# h-bridge_v2.net
KiCad netlist of a schematic drawn in EAGLE
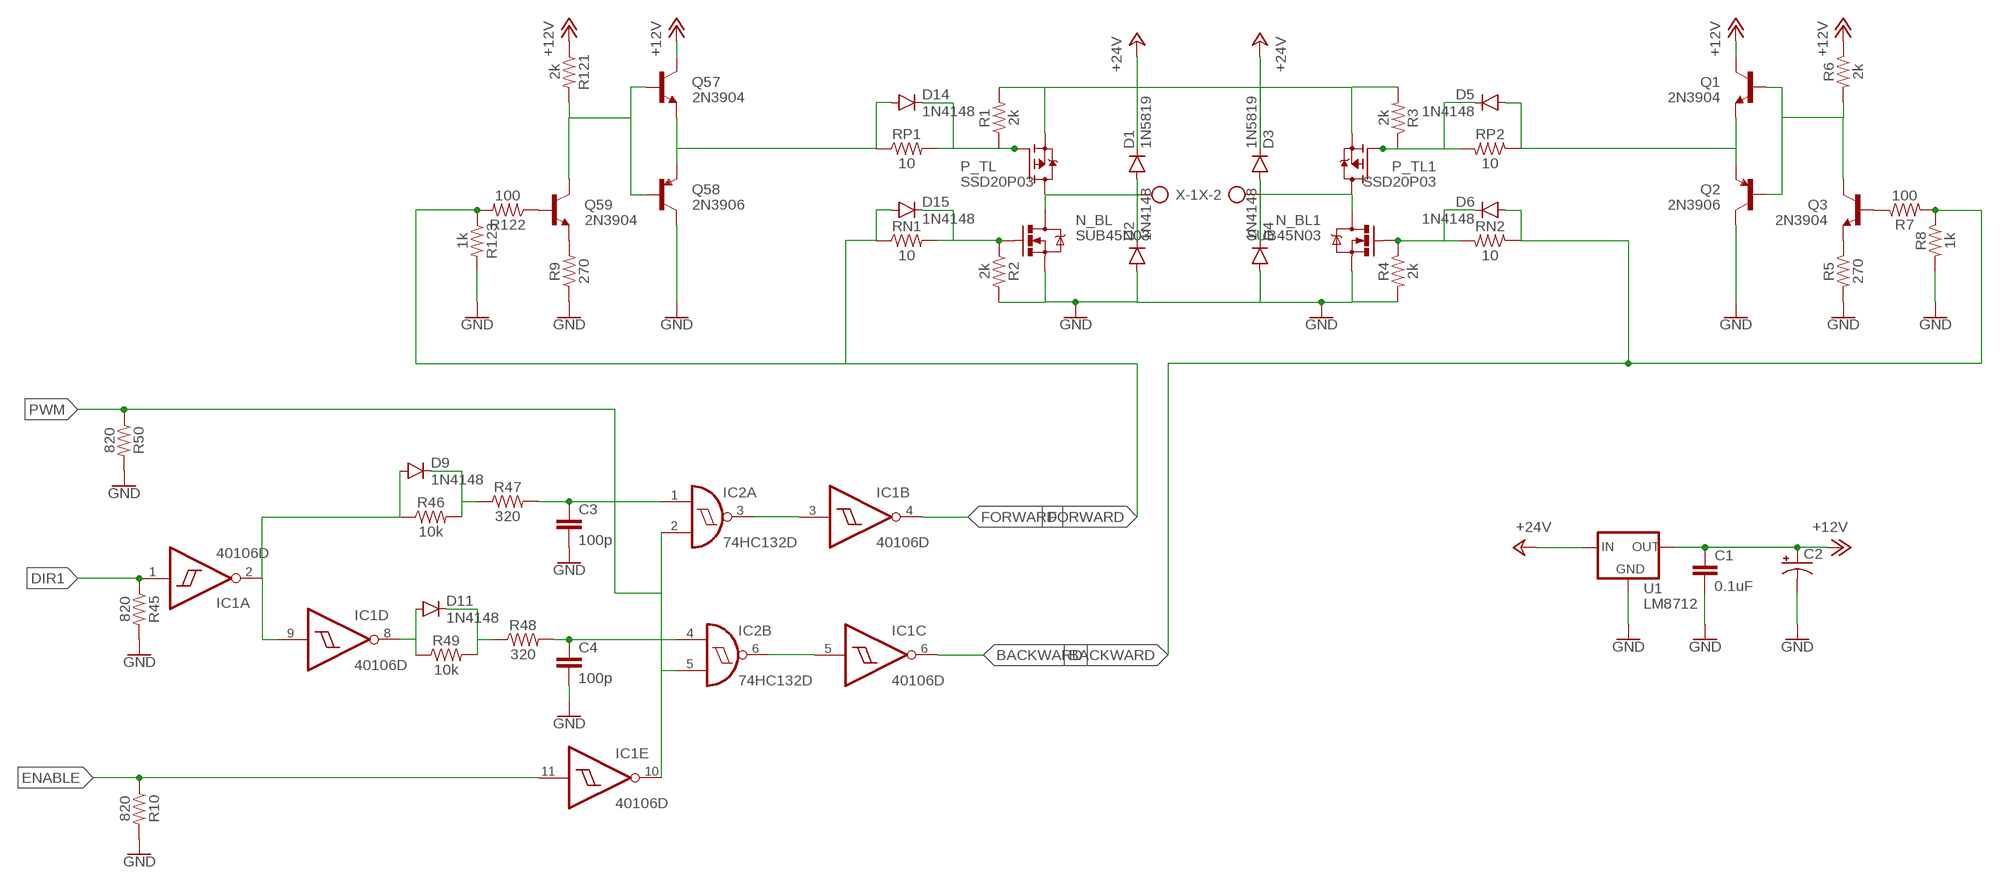
[diagram p0: schematic, sheet 1]

(export (version "E")
  (design (tool "Eeschema 10.0.6"))
  (components
    (comp (ref "C1")
      (value "0.1uF")
      (footprint "eagle-import:0603-CAP")
      (libsource (lib "eagle-import") (part "0.1UF-25V-5%(0603)"))
    )
    (comp (ref "C2")
      (value "CAP_POL1206-KIT")
      (footprint "eagle-import:EIA3216-KIT")
      (libsource (lib "eagle-import") (part "CAP_POL1206-KIT"))
    )
    (comp (ref "C3")
      (value "100p")
      (footprint "eagle-import:0805-CAP")
      (libsource (lib "eagle-import") (part "1.0UF-25V-+80/-20(0805){dblquote}"))
    )
    (comp (ref "C4")
      (value "100p")
      (footprint "eagle-import:0805-CAP")
      (libsource (lib "eagle-import") (part "1.0UF-25V-+80/-20(0805){dblquote}"))
    )
    (comp (ref "D1")
      (value "1N5819")
      (footprint "eagle-import:SOD-123")
      (libsource (lib "eagle-import") (part "DIODESOD123"))
    )
    (comp (ref "D2")
      (value "1N4148")
      (footprint "eagle-import:SOD-123")
      (libsource (lib "eagle-import") (part "DIODESOD123"))
    )
    (comp (ref "D3")
      (value "1N5819")
      (footprint "eagle-import:SOD-123")
      (libsource (lib "eagle-import") (part "DIODESOD123"))
    )
    (comp (ref "D4")
      (value "1N4148")
      (footprint "eagle-import:SOD-123")
      (libsource (lib "eagle-import") (part "DIODESOD123"))
    )
    (comp (ref "D5")
      (value "1N4148")
      (footprint "eagle-import:SOD-123")
      (libsource (lib "eagle-import") (part "DIODESOD123"))
    )
    (comp (ref "D6")
      (value "1N4148")
      (footprint "eagle-import:SOD-123")
      (libsource (lib "eagle-import") (part "DIODESOD123"))
    )
    (comp (ref "D9")
      (value "1N4148")
      (footprint "eagle-import:SOD-123")
      (libsource (lib "eagle-import") (part "DIODESOD123"))
    )
    (comp (ref "D11")
      (value "1N4148")
      (footprint "eagle-import:SOD-123")
      (libsource (lib "eagle-import") (part "DIODESOD123"))
    )
    (comp (ref "D14")
      (value "1N4148")
      (footprint "eagle-import:SOD-123")
      (libsource (lib "eagle-import") (part "DIODESOD123"))
    )
    (comp (ref "D15")
      (value "1N4148")
      (footprint "eagle-import:SOD-123")
      (libsource (lib "eagle-import") (part "DIODESOD123"))
    )
    (comp (ref "IC1")
      (value "40106D")
      (footprint "eagle-import:SO14")
      (libsource (lib "eagle-import") (part "40106D"))
    )
    (comp (ref "IC2")
      (value "74HC132D")
      (footprint "eagle-import:SO14")
      (libsource (lib "eagle-import") (part "74132DHC"))
    )
    (comp (ref "N_BL")
      (value "SUB45N03")
      (footprint "eagle-import:TO-263_D2PAK")
      (libsource (lib "eagle-import") (part "MOSFET-NCHANNELPSMN7R0"))
    )
    (comp (ref "N_BL1")
      (value "SUB45N03")
      (footprint "eagle-import:TO-263_D2PAK")
      (libsource (lib "eagle-import") (part "MOSFET-NCHANNELPSMN7R0"))
    )
    (comp (ref "P_TL")
      (value "SSD20P03")
      (footprint "eagle-import:TO252")
      (libsource (lib "eagle-import") (part "FDD4141TO252"))
    )
    (comp (ref "P_TL1")
      (value "SSD20P03")
      (footprint "eagle-import:TO252")
      (libsource (lib "eagle-import") (part "FDD4141TO252"))
    )
    (comp (ref "Q1")
      (value "2N3904")
      (footprint "eagle-import:SOT23-3")
      (libsource (lib "eagle-import") (part "TRANSISTOR_NPNMMBT5088"))
    )
    (comp (ref "Q2")
      (value "2N3906")
      (footprint "eagle-import:SOT23-3")
      (libsource (lib "eagle-import") (part "TRANSISTOR_PNPPMBT3906"))
    )
    (comp (ref "Q3")
      (value "2N3904")
      (footprint "eagle-import:SOT23-3")
      (libsource (lib "eagle-import") (part "TRANSISTOR_NPNMMBT5088"))
    )
    (comp (ref "Q57")
      (value "2N3904")
      (footprint "eagle-import:SOT23-3")
      (libsource (lib "eagle-import") (part "TRANSISTOR_NPNMMBT5088"))
    )
    (comp (ref "Q58")
      (value "2N3906")
      (footprint "eagle-import:SOT23-3")
      (libsource (lib "eagle-import") (part "TRANSISTOR_PNPPMBT3906"))
    )
    (comp (ref "Q59")
      (value "2N3904")
      (footprint "eagle-import:SOT23-3")
      (libsource (lib "eagle-import") (part "TRANSISTOR_NPNMMBT5088"))
    )
    (comp (ref "R1")
      (value "2k")
      (footprint "eagle-import:AXIAL-0.3")
      (libsource (lib "eagle-import") (part "RESISTORAXIAL-0.3"))
    )
    (comp (ref "R2")
      (value "2k")
      (footprint "eagle-import:AXIAL-0.3")
      (libsource (lib "eagle-import") (part "RESISTORAXIAL-0.3"))
    )
    (comp (ref "R3")
      (value "2k")
      (footprint "eagle-import:AXIAL-0.3")
      (libsource (lib "eagle-import") (part "RESISTORAXIAL-0.3"))
    )
    (comp (ref "R4")
      (value "2k")
      (footprint "eagle-import:AXIAL-0.3")
      (libsource (lib "eagle-import") (part "RESISTORAXIAL-0.3"))
    )
    (comp (ref "R5")
      (value "270")
      (footprint "eagle-import:AXIAL-0.3")
      (libsource (lib "eagle-import") (part "RESISTORAXIAL-0.3"))
    )
    (comp (ref "R6")
      (value "2k")
      (footprint "eagle-import:AXIAL-0.3")
      (libsource (lib "eagle-import") (part "RESISTORAXIAL-0.3"))
    )
    (comp (ref "R7")
      (value "100")
      (footprint "eagle-import:AXIAL-0.3")
      (libsource (lib "eagle-import") (part "RESISTORAXIAL-0.3"))
    )
    (comp (ref "R8")
      (value "1k")
      (footprint "eagle-import:AXIAL-0.3")
      (libsource (lib "eagle-import") (part "RESISTORAXIAL-0.3"))
    )
    (comp (ref "R9")
      (value "270")
      (footprint "eagle-import:AXIAL-0.3")
      (libsource (lib "eagle-import") (part "RESISTORAXIAL-0.3"))
    )
    (comp (ref "R10")
      (value "820")
      (footprint "eagle-import:AXIAL-0.3")
      (libsource (lib "eagle-import") (part "RESISTORAXIAL-0.3"))
    )
    (comp (ref "R45")
      (value "820")
      (footprint "eagle-import:AXIAL-0.3")
      (libsource (lib "eagle-import") (part "RESISTORAXIAL-0.3"))
    )
    (comp (ref "R46")
      (value "10k")
      (footprint "eagle-import:AXIAL-0.3")
      (libsource (lib "eagle-import") (part "RESISTORAXIAL-0.3"))
    )
    (comp (ref "R47")
      (value "320")
      (footprint "eagle-import:AXIAL-0.3")
      (libsource (lib "eagle-import") (part "RESISTORAXIAL-0.3"))
    )
    (comp (ref "R48")
      (value "320")
      (footprint "eagle-import:AXIAL-0.3")
      (libsource (lib "eagle-import") (part "RESISTORAXIAL-0.3"))
    )
    (comp (ref "R49")
      (value "10k")
      (footprint "eagle-import:AXIAL-0.3")
      (libsource (lib "eagle-import") (part "RESISTORAXIAL-0.3"))
    )
    (comp (ref "R50")
      (value "820")
      (footprint "eagle-import:AXIAL-0.3")
      (libsource (lib "eagle-import") (part "RESISTORAXIAL-0.3"))
    )
    (comp (ref "R121")
      (value "2k")
      (footprint "eagle-import:AXIAL-0.3")
      (libsource (lib "eagle-import") (part "RESISTORAXIAL-0.3"))
    )
    (comp (ref "R122")
      (value "100")
      (footprint "eagle-import:AXIAL-0.3")
      (libsource (lib "eagle-import") (part "RESISTORAXIAL-0.3"))
    )
    (comp (ref "R123")
      (value "1k")
      (footprint "eagle-import:AXIAL-0.3")
      (libsource (lib "eagle-import") (part "RESISTORAXIAL-0.3"))
    )
    (comp (ref "RN1")
      (value "10")
      (footprint "eagle-import:AXIAL-0.3")
      (libsource (lib "eagle-import") (part "RESISTORAXIAL-0.3"))
    )
    (comp (ref "RN2")
      (value "10")
      (footprint "eagle-import:AXIAL-0.3")
      (libsource (lib "eagle-import") (part "RESISTORAXIAL-0.3"))
    )
    (comp (ref "RP1")
      (value "10")
      (footprint "eagle-import:AXIAL-0.3")
      (libsource (lib "eagle-import") (part "RESISTORAXIAL-0.3"))
    )
    (comp (ref "RP2")
      (value "10")
      (footprint "eagle-import:AXIAL-0.3")
      (libsource (lib "eagle-import") (part "RESISTORAXIAL-0.3"))
    )
    (comp (ref "U1")
      (value "LM8712")
      (footprint "eagle-import:78XXL")
      (libsource (lib "eagle-import") (part "V_REG_78XXSIDE"))
    )
    (comp (ref "X")
      (value "SMKDSP_1,5/2")
      (footprint "eagle-import:SMKDSP_1,5_2")
      (fields (field (name "MF") "FARNELL") (field (name "MPN") "1733570"))
      (libsource (lib "eagle-import") (part "SMKDSP_1,5/2"))
    )
  )
  (nets
    (net (code "1") (name "+12V") (class "Default")
      (node (ref "C1") (pin "1") (pinfunction "1_1") (pintype "passive"))
      (node (ref "C2") (pin "A") (pinfunction "+_A") (pintype "passive"))
      (node (ref "Q1") (pin "3") (pinfunction "C_3") (pintype "passive"))
      (node (ref "Q57") (pin "3") (pinfunction "C_3") (pintype "passive"))
      (node (ref "R121") (pin "P$1") (pinfunction "1_P$1") (pintype "passive"))
      (node (ref "R6") (pin "P$1") (pinfunction "1_P$1") (pintype "passive"))
      (node (ref "U1") (pin "OUT") (pinfunction "OUT_OUT") (pintype "passive"))
    )
    (net (code "2") (name "+24V") (class "Default")
      (node (ref "D1") (pin "C") (pinfunction "C_C") (pintype "passive"))
      (node (ref "D3") (pin "C") (pinfunction "C_C") (pintype "passive"))
      (node (ref "P_TL") (pin "2") (pinfunction "S_2") (pintype "passive"))
      (node (ref "P_TL1") (pin "2") (pinfunction "S_2") (pintype "passive"))
      (node (ref "R1") (pin "P$2") (pinfunction "2_P$2") (pintype "passive"))
      (node (ref "R3") (pin "P$2") (pinfunction "2_P$2") (pintype "passive"))
      (node (ref "U1") (pin "IN") (pinfunction "IN_IN") (pintype "input"))
    )
    (net (code "3") (name "BACKWARD") (class "Default")
      (node (ref "D6") (pin "A") (pinfunction "A_A") (pintype "passive"))
      (node (ref "IC1") (pin "6") (pinfunction "O_6") (pintype "output"))
      (node (ref "R7") (pin "P$2") (pinfunction "2_P$2") (pintype "passive"))
      (node (ref "R8") (pin "P$1") (pinfunction "1_P$1") (pintype "passive"))
      (node (ref "RN2") (pin "P$1") (pinfunction "1_P$1") (pintype "passive"))
    )
    (net (code "4") (name "DIR1") (class "Default")
      (node (ref "IC1") (pin "1") (pinfunction "I_1") (pintype "input"))
      (node (ref "R45") (pin "P$1") (pinfunction "1_P$1") (pintype "passive"))
    )
    (net (code "5") (name "ENABLE") (class "Default")
      (node (ref "IC1") (pin "11") (pinfunction "I_11") (pintype "input"))
      (node (ref "R10") (pin "P$1") (pinfunction "1_P$1") (pintype "passive"))
    )
    (net (code "6") (name "FORWARD") (class "Default")
      (node (ref "D15") (pin "A") (pinfunction "A_A") (pintype "passive"))
      (node (ref "IC1") (pin "4") (pinfunction "O_4") (pintype "output"))
      (node (ref "R122") (pin "P$2") (pinfunction "2_P$2") (pintype "passive"))
      (node (ref "R123") (pin "P$1") (pinfunction "1_P$1") (pintype "passive"))
      (node (ref "RN1") (pin "P$1") (pinfunction "1_P$1") (pintype "passive"))
    )
    (net (code "7") (name "GND") (class "Default")
      (node (ref "C1") (pin "2") (pinfunction "2_2") (pintype "passive"))
      (node (ref "C2") (pin "C") (pinfunction "-_C") (pintype "passive"))
      (node (ref "C3") (pin "2") (pinfunction "2_2") (pintype "passive"))
      (node (ref "C4") (pin "2") (pinfunction "2_2") (pintype "passive"))
      (node (ref "D2") (pin "A") (pinfunction "A_A") (pintype "passive"))
      (node (ref "D4") (pin "A") (pinfunction "A_A") (pintype "passive"))
      (node (ref "N_BL") (pin "3") (pinfunction "S_3") (pintype "passive"))
      (node (ref "N_BL1") (pin "3") (pinfunction "S_3") (pintype "passive"))
      (node (ref "Q2") (pin "3") (pinfunction "C_3") (pintype "passive"))
      (node (ref "Q58") (pin "3") (pinfunction "C_3") (pintype "passive"))
      (node (ref "R10") (pin "P$2") (pinfunction "2_P$2") (pintype "passive"))
      (node (ref "R123") (pin "P$2") (pinfunction "2_P$2") (pintype "passive"))
      (node (ref "R2") (pin "P$2") (pinfunction "2_P$2") (pintype "passive"))
      (node (ref "R4") (pin "P$2") (pinfunction "2_P$2") (pintype "passive"))
      (node (ref "R45") (pin "P$2") (pinfunction "2_P$2") (pintype "passive"))
      (node (ref "R5") (pin "P$2") (pinfunction "2_P$2") (pintype "passive"))
      (node (ref "R50") (pin "P$2") (pinfunction "2_P$2") (pintype "passive"))
      (node (ref "R8") (pin "P$2") (pinfunction "2_P$2") (pintype "passive"))
      (node (ref "R9") (pin "P$1") (pinfunction "1_P$1") (pintype "passive"))
      (node (ref "U1") (pin "GND") (pinfunction "GND_GND") (pintype "input"))
    )
    (net (code "8") (name "Net-(IC1A-O)") (class "Default")
      (node (ref "D9") (pin "A") (pinfunction "A_A") (pintype "passive"))
      (node (ref "IC1") (pin "2") (pinfunction "O_2") (pintype "output"))
      (node (ref "IC1") (pin "9") (pinfunction "I_9") (pintype "input"))
      (node (ref "R46") (pin "P$1") (pinfunction "1_P$1") (pintype "passive"))
    )
    (net (code "9") (name "Net-(IC1B-I)") (class "Default")
      (node (ref "IC1") (pin "3") (pinfunction "I_3") (pintype "input"))
      (node (ref "IC2") (pin "3") (pinfunction "O_3") (pintype "output"))
    )
    (net (code "10") (name "Net-(IC1C-I)") (class "Default")
      (node (ref "IC1") (pin "5") (pinfunction "I_5") (pintype "input"))
      (node (ref "IC2") (pin "6") (pinfunction "O_6") (pintype "output"))
    )
    (net (code "11") (name "Net-(IC1D-O)") (class "Default")
      (node (ref "D11") (pin "A") (pinfunction "A_A") (pintype "passive"))
      (node (ref "IC1") (pin "8") (pinfunction "O_8") (pintype "output"))
      (node (ref "R49") (pin "P$1") (pinfunction "1_P$1") (pintype "passive"))
    )
    (net (code "12") (name "Net-(IC2A-I0)") (class "Default")
      (node (ref "C3") (pin "1") (pinfunction "1_1") (pintype "passive"))
      (node (ref "IC2") (pin "1") (pinfunction "I0_1") (pintype "input"))
      (node (ref "R47") (pin "P$2") (pinfunction "2_P$2") (pintype "passive"))
    )
    (net (code "13") (name "Net-(IC2B-I0)") (class "Default")
      (node (ref "C4") (pin "1") (pinfunction "1_1") (pintype "passive"))
      (node (ref "IC2") (pin "4") (pinfunction "I0_4") (pintype "input"))
      (node (ref "R48") (pin "P$2") (pinfunction "2_P$2") (pintype "passive"))
    )
    (net (code "14") (name "Net-(N_BL-D)") (class "Default")
      (node (ref "D1") (pin "A") (pinfunction "A_A") (pintype "passive"))
      (node (ref "D2") (pin "C") (pinfunction "C_C") (pintype "passive"))
      (node (ref "N_BL") (pin "2") (pinfunction "D_2") (pintype "passive"))
      (node (ref "P_TL") (pin "3") (pinfunction "D_3") (pintype "passive"))
      (node (ref "X") (pin "1") (pinfunction "KL_1") (pintype "passive"))
    )
    (net (code "15") (name "Net-(N_BL-G)") (class "Default")
      (node (ref "D15") (pin "C") (pinfunction "C_C") (pintype "passive"))
      (node (ref "N_BL") (pin "1") (pinfunction "G_1") (pintype "passive"))
      (node (ref "R2") (pin "P$1") (pinfunction "1_P$1") (pintype "passive"))
      (node (ref "RN1") (pin "P$2") (pinfunction "2_P$2") (pintype "passive"))
    )
    (net (code "16") (name "Net-(N_BL1-D)") (class "Default")
      (node (ref "D3") (pin "A") (pinfunction "A_A") (pintype "passive"))
      (node (ref "D4") (pin "C") (pinfunction "C_C") (pintype "passive"))
      (node (ref "N_BL1") (pin "2") (pinfunction "D_2") (pintype "passive"))
      (node (ref "P_TL1") (pin "3") (pinfunction "D_3") (pintype "passive"))
      (node (ref "X") (pin "2") (pinfunction "KL_2") (pintype "passive"))
    )
    (net (code "17") (name "Net-(N_BL1-G)") (class "Default")
      (node (ref "D6") (pin "C") (pinfunction "C_C") (pintype "passive"))
      (node (ref "N_BL1") (pin "1") (pinfunction "G_1") (pintype "passive"))
      (node (ref "R4") (pin "P$1") (pinfunction "1_P$1") (pintype "passive"))
      (node (ref "RN2") (pin "P$2") (pinfunction "2_P$2") (pintype "passive"))
    )
    (net (code "18") (name "Net-(P_TL-G)") (class "Default")
      (node (ref "D14") (pin "C") (pinfunction "C_C") (pintype "passive"))
      (node (ref "P_TL") (pin "1") (pinfunction "G_1") (pintype "passive"))
      (node (ref "R1") (pin "P$1") (pinfunction "1_P$1") (pintype "passive"))
      (node (ref "RP1") (pin "P$2") (pinfunction "2_P$2") (pintype "passive"))
    )
    (net (code "19") (name "Net-(P_TL1-G)") (class "Default")
      (node (ref "D5") (pin "C") (pinfunction "C_C") (pintype "passive"))
      (node (ref "P_TL1") (pin "1") (pinfunction "G_1") (pintype "passive"))
      (node (ref "R3") (pin "P$1") (pinfunction "1_P$1") (pintype "passive"))
      (node (ref "RP2") (pin "P$2") (pinfunction "2_P$2") (pintype "passive"))
    )
    (net (code "20") (name "Net-(Q1-B)") (class "Default")
      (node (ref "Q1") (pin "1") (pinfunction "B_1") (pintype "passive"))
      (node (ref "Q2") (pin "1") (pinfunction "B_1") (pintype "passive"))
      (node (ref "Q3") (pin "3") (pinfunction "C_3") (pintype "passive"))
      (node (ref "R6") (pin "P$2") (pinfunction "2_P$2") (pintype "passive"))
    )
    (net (code "21") (name "Net-(Q1-E)") (class "Default")
      (node (ref "D5") (pin "A") (pinfunction "A_A") (pintype "passive"))
      (node (ref "Q1") (pin "2") (pinfunction "E_2") (pintype "passive"))
      (node (ref "Q2") (pin "2") (pinfunction "E_2") (pintype "passive"))
      (node (ref "RP2") (pin "P$1") (pinfunction "1_P$1") (pintype "passive"))
    )
    (net (code "22") (name "Net-(Q3-B)") (class "Default")
      (node (ref "Q3") (pin "1") (pinfunction "B_1") (pintype "passive"))
      (node (ref "R7") (pin "P$1") (pinfunction "1_P$1") (pintype "passive"))
    )
    (net (code "23") (name "Net-(Q3-E)") (class "Default")
      (node (ref "Q3") (pin "2") (pinfunction "E_2") (pintype "passive"))
      (node (ref "R5") (pin "P$1") (pinfunction "1_P$1") (pintype "passive"))
    )
    (net (code "24") (name "Net-(Q57-B)") (class "Default")
      (node (ref "Q57") (pin "1") (pinfunction "B_1") (pintype "passive"))
      (node (ref "Q58") (pin "1") (pinfunction "B_1") (pintype "passive"))
      (node (ref "Q59") (pin "3") (pinfunction "C_3") (pintype "passive"))
      (node (ref "R121") (pin "P$2") (pinfunction "2_P$2") (pintype "passive"))
    )
    (net (code "25") (name "Net-(Q57-E)") (class "Default")
      (node (ref "D14") (pin "A") (pinfunction "A_A") (pintype "passive"))
      (node (ref "Q57") (pin "2") (pinfunction "E_2") (pintype "passive"))
      (node (ref "Q58") (pin "2") (pinfunction "E_2") (pintype "passive"))
      (node (ref "RP1") (pin "P$1") (pinfunction "1_P$1") (pintype "passive"))
    )
    (net (code "26") (name "Net-(Q59-B)") (class "Default")
      (node (ref "Q59") (pin "1") (pinfunction "B_1") (pintype "passive"))
      (node (ref "R122") (pin "P$1") (pinfunction "1_P$1") (pintype "passive"))
    )
    (net (code "27") (name "Net-(Q59-E)") (class "Default")
      (node (ref "Q59") (pin "2") (pinfunction "E_2") (pintype "passive"))
      (node (ref "R9") (pin "P$2") (pinfunction "2_P$2") (pintype "passive"))
    )
    (net (code "28") (name "Net-(R46-2)") (class "Default")
      (node (ref "D9") (pin "C") (pinfunction "C_C") (pintype "passive"))
      (node (ref "R46") (pin "P$2") (pinfunction "2_P$2") (pintype "passive"))
      (node (ref "R47") (pin "P$1") (pinfunction "1_P$1") (pintype "passive"))
    )
    (net (code "29") (name "Net-(R48-1)") (class "Default")
      (node (ref "D11") (pin "C") (pinfunction "C_C") (pintype "passive"))
      (node (ref "R48") (pin "P$1") (pinfunction "1_P$1") (pintype "passive"))
      (node (ref "R49") (pin "P$2") (pinfunction "2_P$2") (pintype "passive"))
    )
    (net (code "30") (name "PWM") (class "Default")
      (node (ref "IC1") (pin "10") (pinfunction "O_10") (pintype "output"))
      (node (ref "IC2") (pin "2") (pinfunction "I1_2") (pintype "input"))
      (node (ref "IC2") (pin "5") (pinfunction "I1_5") (pintype "input"))
      (node (ref "R50") (pin "P$1") (pinfunction "1_P$1") (pintype "passive"))
    )
  )
)
